# Check-Sheet.net
KiCad netlist of a schematic drawn in Altium Designer
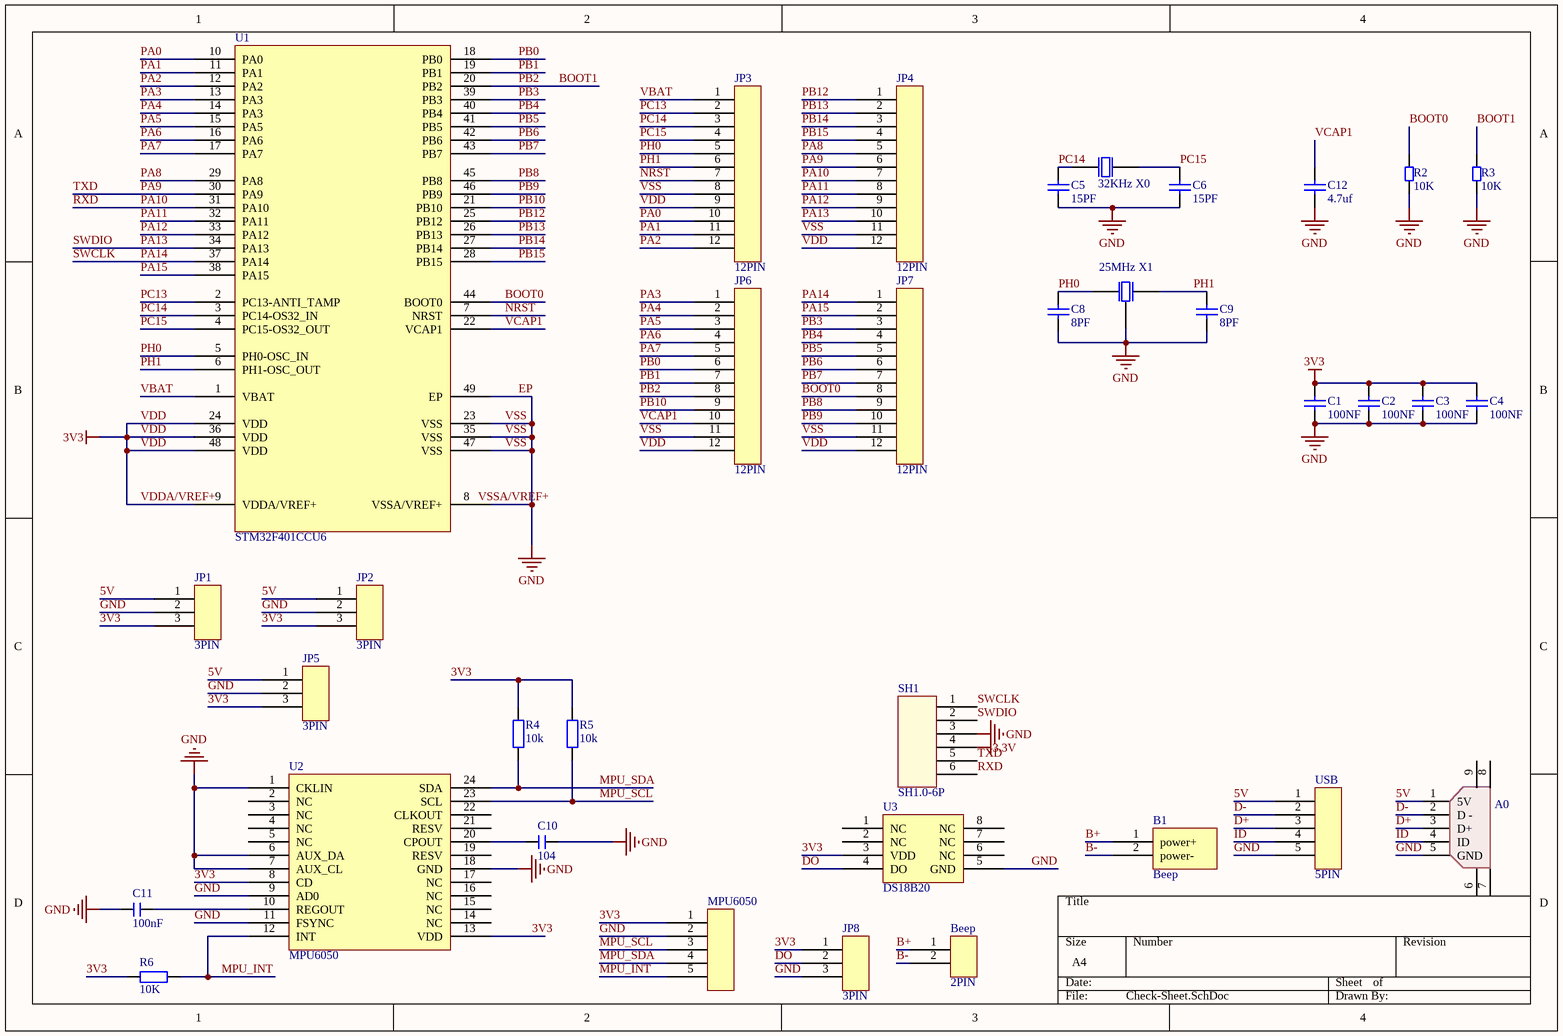
[diagram p0: Check-Sheet.SchDoc]

(export (version "E")
  (design (tool "Eeschema 10.0.6"))
  (components
    (comp (ref "25MHz X1")
      (value "XTAL 3225 8M")
      (footprint "OSC 3225-4P")
      (libsource (lib "tianxiaohua_Schlib") (part "XTAL 3225 8M"))
    )
    (comp (ref "32KHz X0")
      (value "XTAL 3215 32.768kKHz")
      (footprint "OSC 3215-2P")
      (libsource (lib "tianxiaohua_Schlib") (part "XTAL 3215 32.768kKHz"))
    )
    (comp (ref "A0")
      (value "Micro USB")
      (footprint "USB-micro_A")
      (libsource (lib "Schlib1") (part "Micro USB"))
    )
    (comp (ref "B1") (value "Beep") (footprint "5020beep") (libsource (lib "Schlib1") (part "Beep")))
    (comp (ref "Beep") (value "2PIN") (footprint "2PIN") (libsource (lib "Schlib1") (part "2PIN")))
    (comp (ref "C1")
      (value "100NF")
      (footprint "C 0603_M")
      (libsource (lib "tianxiaohua_Schlib") (part "0402 CAP"))
    )
    (comp (ref "C2")
      (value "100NF")
      (footprint "C 0603_M")
      (libsource (lib "tianxiaohua_Schlib") (part "0402 CAP"))
    )
    (comp (ref "C3")
      (value "100NF")
      (footprint "C 0603_M")
      (libsource (lib "tianxiaohua_Schlib") (part "0402 CAP"))
    )
    (comp (ref "C4")
      (value "100NF")
      (footprint "C 0603_M")
      (libsource (lib "tianxiaohua_Schlib") (part "0402 CAP"))
    )
    (comp (ref "C5")
      (value "15PF")
      (footprint "C 0603_M")
      (libsource (lib "tianxiaohua_Schlib") (part "0402 CAP"))
    )
    (comp (ref "C6")
      (value "15PF")
      (footprint "C 0603_M")
      (libsource (lib "tianxiaohua_Schlib") (part "0402 CAP"))
    )
    (comp (ref "C8")
      (value "8PF")
      (footprint "C 0603_M")
      (libsource (lib "tianxiaohua_Schlib") (part "0402 CAP"))
    )
    (comp (ref "C9")
      (value "8PF")
      (footprint "C 0603_M")
      (libsource (lib "tianxiaohua_Schlib") (part "0402 CAP"))
    )
    (comp (ref "C10")
      (value "104")
      (footprint "C 0805_L")
      (description "无极性贴片电容")
      (fields (field (name "版权归属") "源创客"))
      (libsource (lib "3.1   - 电阻-电容-电感") (part "C"))
    )
    (comp (ref "C11")
      (value "100nF")
      (footprint "C 0805_L")
      (description "无极性贴片电容")
      (fields (field (name "版权归属") "源创客"))
      (libsource (lib "3.1   - 电阻-电容-电感") (part "C"))
    )
    (comp (ref "C12")
      (value "4.7uf")
      (footprint "C 0603_M")
      (description "Polarized Capacitor (Radial)")
      (fields (field (name "Comment") "Cap Chip 0603") (field (name "PUBLISHER") "Altium Limited"))
      (libsource (lib "tianxiaohua_Schlib") (part "Cap Chip 0603"))
    )
    (comp (ref "JP1") (value "3PIN") (footprint "3pin") (libsource (lib "Schlib1") (part "3PIN")))
    (comp (ref "JP2") (value "3PIN") (footprint "3pin") (libsource (lib "Schlib1") (part "3PIN")))
    (comp (ref "JP3") (value "12PIN") (footprint "12PIN") (libsource (lib "Schlib1") (part "12PIN")))
    (comp (ref "JP4") (value "12PIN") (footprint "12PIN") (libsource (lib "Schlib1") (part "12PIN")))
    (comp (ref "JP5") (value "3PIN") (footprint "3pin") (libsource (lib "Schlib1") (part "3PIN")))
    (comp (ref "JP6") (value "12PIN") (footprint "12PIN") (libsource (lib "Schlib1") (part "12PIN")))
    (comp (ref "JP7") (value "12PIN") (footprint "12PIN") (libsource (lib "Schlib1") (part "12PIN")))
    (comp (ref "JP8") (value "3PIN") (footprint "3pin") (libsource (lib "Schlib1") (part "3PIN")))
    (comp (ref "MPU6050") (value "5PIN") (footprint "5PIN") (libsource (lib "Schlib1") (part "5PIN")))
    (comp (ref "R2")
      (value "10K")
      (footprint "R 0603_M")
      (libsource (lib "tianxiaohua_Schlib") (part "0402 RES"))
    )
    (comp (ref "R3")
      (value "10K")
      (footprint "R 0603_M")
      (libsource (lib "tianxiaohua_Schlib") (part "0402 RES"))
    )
    (comp (ref "R4")
      (value "10k")
      (footprint "0603R")
      (description "贴片电阻")
      (fields (field (name "版权归属") "源创客"))
      (libsource (lib "3.1   - 电阻-电容-电感") (part "R"))
    )
    (comp (ref "R5")
      (value "10k")
      (footprint "0603R")
      (description "贴片电阻")
      (fields (field (name "版权归属") "源创客"))
      (libsource (lib "3.1   - 电阻-电容-电感") (part "R"))
    )
    (comp (ref "R6")
      (value "10K")
      (footprint "0603R")
      (description "贴片电阻")
      (fields (field (name "版权归属") "源创客"))
      (libsource (lib "3.1   - 电阻-电容-电感") (part "R"))
    )
    (comp (ref "SH1")
      (value "SH1.0-6P")
      (footprint "6PIN")
      (description "间距为1mm的端子")
      (libsource (lib "tianxiaohua_Schlib") (part "SH1.0-6P"))
    )
    (comp (ref "U1")
      (value "STM32F401CCU6")
      (footprint "QFN48 7X7_M")
      (libsource (lib "Schlib1") (part "STM32F401CCU6"))
    )
    (comp (ref "U2") (value "MPU6050") (footprint "QFN24") (libsource (lib "Schlib1") (part "MPU6050")))
    (comp (ref "U3") (value "DS18B20") (footprint "SOP8") (libsource (lib "Schlib1") (part "DS18B20")))
    (comp (ref "USB") (value "5PIN") (footprint "5PIN") (libsource (lib "Schlib1") (part "5PIN")))
  )
  (nets
    (net (code "1") (name "/5V") (class "Default")
      (node (ref "A0") (pin "1") (pinfunction "5V_1") (pintype "passive"))
      (node (ref "JP1") (pin "1") (pintype "passive"))
      (node (ref "JP2") (pin "1") (pintype "passive"))
      (node (ref "JP5") (pin "1") (pintype "passive"))
      (node (ref "USB") (pin "1") (pintype "passive"))
    )
    (net (code "2") (name "/B+") (class "Default")
      (node (ref "B1") (pin "1") (pinfunction "power+_1") (pintype "passive"))
      (node (ref "Beep") (pin "1") (pintype "passive"))
    )
    (net (code "3") (name "/B-") (class "Default")
      (node (ref "B1") (pin "2") (pinfunction "power-_2") (pintype "passive"))
      (node (ref "Beep") (pin "2") (pintype "passive"))
    )
    (net (code "4") (name "/BOOT0") (class "Default")
      (node (ref "JP7") (pin "8") (pintype "passive"))
      (node (ref "R2") (pin "2") (pinfunction "2_2") (pintype "passive"))
      (node (ref "U1") (pin "44") (pinfunction "BOOT0_44") (pintype "passive"))
    )
    (net (code "5") (name "/BOOT1") (class "Default")
      (node (ref "JP6") (pin "8") (pintype "passive"))
      (node (ref "R3") (pin "2") (pinfunction "2_2") (pintype "passive"))
      (node (ref "U1") (pin "20") (pinfunction "PB2_20") (pintype "passive"))
    )
    (net (code "6") (name "/D+") (class "Default")
      (node (ref "A0") (pin "3") (pinfunction "D+_3") (pintype "passive"))
      (node (ref "USB") (pin "3") (pintype "passive"))
    )
    (net (code "7") (name "/D-") (class "Default")
      (node (ref "A0") (pin "2") (pinfunction "D_-_2") (pintype "passive"))
      (node (ref "USB") (pin "2") (pintype "passive"))
    )
    (net (code "8") (name "/DO") (class "Default")
      (node (ref "JP8") (pin "2") (pintype "passive"))
      (node (ref "U3") (pin "4") (pinfunction "DO_4") (pintype "passive"))
    )
    (net (code "9") (name "/ID") (class "Default")
      (node (ref "A0") (pin "4") (pinfunction "ID_4") (pintype "passive"))
      (node (ref "USB") (pin "4") (pintype "passive"))
    )
    (net (code "10") (name "/MPU_INT") (class "Default")
      (node (ref "MPU6050") (pin "5") (pintype "passive"))
      (node (ref "R6") (pin "2") (pinfunction "2_2") (pintype "passive"))
      (node (ref "U2") (pin "12") (pinfunction "INT_12") (pintype "passive"))
    )
    (net (code "11") (name "/MPU_SCL") (class "Default")
      (node (ref "MPU6050") (pin "3") (pintype "passive"))
      (node (ref "R5") (pin "1") (pinfunction "1_1") (pintype "passive"))
      (node (ref "U2") (pin "23") (pinfunction "SCL_23") (pintype "passive"))
    )
    (net (code "12") (name "/MPU_SDA") (class "Default")
      (node (ref "MPU6050") (pin "4") (pintype "passive"))
      (node (ref "R4") (pin "1") (pinfunction "1_1") (pintype "passive"))
      (node (ref "U2") (pin "24") (pinfunction "SDA_24") (pintype "passive"))
    )
    (net (code "13") (name "/NRST") (class "Default")
      (node (ref "JP3") (pin "7") (pintype "passive"))
      (node (ref "U1") (pin "7") (pinfunction "NRST_7") (pintype "passive"))
    )
    (net (code "14") (name "/PA0") (class "Default")
      (node (ref "JP3") (pin "10") (pintype "passive"))
      (node (ref "U1") (pin "10") (pinfunction "PA0_10") (pintype "passive"))
    )
    (net (code "15") (name "/PA1") (class "Default")
      (node (ref "JP3") (pin "11") (pintype "passive"))
      (node (ref "U1") (pin "11") (pinfunction "PA1_11") (pintype "passive"))
    )
    (net (code "16") (name "/PA2") (class "Default")
      (node (ref "JP3") (pin "12") (pintype "passive"))
      (node (ref "U1") (pin "12") (pinfunction "PA2_12") (pintype "passive"))
    )
    (net (code "17") (name "/PA3") (class "Default")
      (node (ref "JP6") (pin "1") (pintype "passive"))
      (node (ref "U1") (pin "13") (pinfunction "PA3_13") (pintype "passive"))
    )
    (net (code "18") (name "/PA4") (class "Default")
      (node (ref "JP6") (pin "2") (pintype "passive"))
      (node (ref "U1") (pin "14") (pinfunction "PA3_14") (pintype "passive"))
    )
    (net (code "19") (name "/PA5") (class "Default")
      (node (ref "JP6") (pin "3") (pintype "passive"))
      (node (ref "U1") (pin "15") (pinfunction "PA5_15") (pintype "passive"))
    )
    (net (code "20") (name "/PA6") (class "Default")
      (node (ref "JP6") (pin "4") (pintype "passive"))
      (node (ref "U1") (pin "16") (pinfunction "PA6_16") (pintype "passive"))
    )
    (net (code "21") (name "/PA7") (class "Default")
      (node (ref "JP6") (pin "5") (pintype "passive"))
      (node (ref "U1") (pin "17") (pinfunction "PA7_17") (pintype "passive"))
    )
    (net (code "22") (name "/PA8") (class "Default")
      (node (ref "JP4") (pin "5") (pintype "passive"))
      (node (ref "U1") (pin "29") (pinfunction "PA8_29") (pintype "passive"))
    )
    (net (code "23") (name "/PA9") (class "Default")
      (node (ref "JP4") (pin "6") (pintype "passive"))
      (node (ref "SH1") (pin "5") (pintype "passive"))
      (node (ref "U1") (pin "30") (pinfunction "PA9_30") (pintype "passive"))
    )
    (net (code "24") (name "/PA10") (class "Default")
      (node (ref "JP4") (pin "7") (pintype "passive"))
      (node (ref "SH1") (pin "6") (pinfunction "6_6") (pintype "passive"))
      (node (ref "U1") (pin "31") (pinfunction "PA10_31") (pintype "passive"))
    )
    (net (code "25") (name "/PA11") (class "Default")
      (node (ref "JP4") (pin "8") (pintype "passive"))
      (node (ref "U1") (pin "32") (pinfunction "PA11_32") (pintype "passive"))
    )
    (net (code "26") (name "/PA12") (class "Default")
      (node (ref "JP4") (pin "9") (pintype "passive"))
      (node (ref "U1") (pin "33") (pinfunction "PA12_33") (pintype "passive"))
    )
    (net (code "27") (name "/PA13") (class "Default")
      (node (ref "JP4") (pin "10") (pintype "passive"))
      (node (ref "SH1") (pin "2") (pinfunction "2_2") (pintype "passive"))
      (node (ref "U1") (pin "34") (pinfunction "PA13_34") (pintype "passive"))
    )
    (net (code "28") (name "/PA14") (class "Default")
      (node (ref "JP7") (pin "1") (pintype "passive"))
      (node (ref "SH1") (pin "1") (pintype "passive"))
      (node (ref "U1") (pin "37") (pinfunction "PA14_37") (pintype "passive"))
    )
    (net (code "29") (name "/PA15") (class "Default")
      (node (ref "JP7") (pin "2") (pintype "passive"))
      (node (ref "U1") (pin "38") (pinfunction "PA15_38") (pintype "passive"))
    )
    (net (code "30") (name "/PB0") (class "Default")
      (node (ref "JP6") (pin "6") (pintype "passive"))
      (node (ref "U1") (pin "18") (pinfunction "PB0_18") (pintype "passive"))
    )
    (net (code "31") (name "/PB1") (class "Default")
      (node (ref "JP6") (pin "7") (pintype "passive"))
      (node (ref "U1") (pin "19") (pinfunction "PB1_19") (pintype "passive"))
    )
    (net (code "32") (name "/PB3") (class "Default")
      (node (ref "JP7") (pin "3") (pintype "passive"))
      (node (ref "U1") (pin "39") (pinfunction "PB3_39") (pintype "passive"))
    )
    (net (code "33") (name "/PB4") (class "Default")
      (node (ref "JP7") (pin "4") (pintype "passive"))
      (node (ref "U1") (pin "40") (pinfunction "PB4_40") (pintype "passive"))
    )
    (net (code "34") (name "/PB5") (class "Default")
      (node (ref "JP7") (pin "5") (pintype "passive"))
      (node (ref "U1") (pin "41") (pinfunction "PB5_41") (pintype "passive"))
    )
    (net (code "35") (name "/PB6") (class "Default")
      (node (ref "JP7") (pin "6") (pintype "passive"))
      (node (ref "U1") (pin "42") (pinfunction "PB6_42") (pintype "passive"))
    )
    (net (code "36") (name "/PB7") (class "Default")
      (node (ref "JP7") (pin "7") (pintype "passive"))
      (node (ref "U1") (pin "43") (pinfunction "PB7_43") (pintype "passive"))
    )
    (net (code "37") (name "/PB8") (class "Default")
      (node (ref "JP7") (pin "9") (pintype "passive"))
      (node (ref "U1") (pin "45") (pinfunction "PB8_45") (pintype "passive"))
    )
    (net (code "38") (name "/PB9") (class "Default")
      (node (ref "JP7") (pin "10") (pintype "passive"))
      (node (ref "U1") (pin "46") (pinfunction "PB9_46") (pintype "passive"))
    )
    (net (code "39") (name "/PB10") (class "Default")
      (node (ref "JP6") (pin "9") (pintype "passive"))
      (node (ref "U1") (pin "21") (pinfunction "PB10_21") (pintype "passive"))
    )
    (net (code "40") (name "/PB12") (class "Default")
      (node (ref "JP4") (pin "1") (pintype "passive"))
      (node (ref "U1") (pin "25") (pinfunction "PB12_25") (pintype "passive"))
    )
    (net (code "41") (name "/PB13") (class "Default")
      (node (ref "JP4") (pin "2") (pintype "passive"))
      (node (ref "U1") (pin "26") (pinfunction "PB13_26") (pintype "passive"))
    )
    (net (code "42") (name "/PB14") (class "Default")
      (node (ref "JP4") (pin "3") (pintype "passive"))
      (node (ref "U1") (pin "27") (pinfunction "PB14_27") (pintype "passive"))
    )
    (net (code "43") (name "/PB15") (class "Default")
      (node (ref "JP4") (pin "4") (pintype "passive"))
      (node (ref "U1") (pin "28") (pinfunction "PB15_28") (pintype "passive"))
    )
    (net (code "44") (name "/PC13") (class "Default")
      (node (ref "JP3") (pin "2") (pintype "passive"))
      (node (ref "U1") (pin "2") (pinfunction "PC13-ANTI_TAMP_2") (pintype "passive"))
    )
    (net (code "45") (name "/PC14") (class "Default")
      (node (ref "32KHz X0") (pin "1") (pinfunction "OSC1_1") (pintype "passive"))
      (node (ref "C5") (pin "2") (pinfunction "2_2") (pintype "passive"))
      (node (ref "JP3") (pin "3") (pintype "passive"))
      (node (ref "U1") (pin "3") (pinfunction "PC14-OS32_IN_3") (pintype "passive"))
    )
    (net (code "46") (name "/PC15") (class "Default")
      (node (ref "32KHz X0") (pin "2") (pinfunction "OSC2_2") (pintype "passive"))
      (node (ref "C6") (pin "2") (pinfunction "2_2") (pintype "passive"))
      (node (ref "JP3") (pin "4") (pintype "passive"))
      (node (ref "U1") (pin "4") (pinfunction "PC15-OS32_OUT_4") (pintype "passive"))
    )
    (net (code "47") (name "/PH0") (class "Default")
      (node (ref "25MHz X1") (pin "1") (pinfunction "OSC1_1") (pintype "passive"))
      (node (ref "C8") (pin "2") (pinfunction "2_2") (pintype "passive"))
      (node (ref "JP3") (pin "5") (pintype "passive"))
      (node (ref "U1") (pin "5") (pinfunction "PH0-OSC_IN_5") (pintype "passive"))
    )
    (net (code "48") (name "/PH1") (class "Default")
      (node (ref "25MHz X1") (pin "2") (pinfunction "OSC2_2") (pintype "passive"))
      (node (ref "C9") (pin "2") (pinfunction "2_2") (pintype "passive"))
      (node (ref "JP3") (pin "6") (pintype "passive"))
      (node (ref "U1") (pin "6") (pinfunction "PH1-OSC_OUT_6") (pintype "passive"))
    )
    (net (code "49") (name "/VBAT") (class "Default")
      (node (ref "JP3") (pin "1") (pintype "passive"))
      (node (ref "U1") (pin "1") (pinfunction "VBAT_1") (pintype "passive"))
    )
    (net (code "50") (name "/VCAP1") (class "Default")
      (node (ref "C12") (pin "2") (pinfunction "2_2") (pintype "passive"))
      (node (ref "JP6") (pin "10") (pintype "passive"))
      (node (ref "U1") (pin "22") (pinfunction "VCAP1_22") (pintype "passive"))
    )
    (net (code "52") (name "3.3V") (class "Default")
      (node (ref "SH1") (pin "4") (pinfunction "4_4") (pintype "passive"))
    )
    (net (code "53") (name "3V3") (class "Default")
      (node (ref "C1") (pin "2") (pinfunction "2_2") (pintype "passive"))
      (node (ref "C2") (pin "2") (pinfunction "2_2") (pintype "passive"))
      (node (ref "C3") (pin "2") (pinfunction "2_2") (pintype "passive"))
      (node (ref "C4") (pin "2") (pinfunction "2_2") (pintype "passive"))
      (node (ref "JP1") (pin "3") (pintype "passive"))
      (node (ref "JP2") (pin "3") (pintype "passive"))
      (node (ref "JP3") (pin "9") (pintype "passive"))
      (node (ref "JP4") (pin "12") (pintype "passive"))
      (node (ref "JP5") (pin "3") (pintype "passive"))
      (node (ref "JP6") (pin "12") (pintype "passive"))
      (node (ref "JP7") (pin "12") (pintype "passive"))
      (node (ref "JP8") (pin "1") (pintype "passive"))
      (node (ref "MPU6050") (pin "1") (pintype "passive"))
      (node (ref "R4") (pin "2") (pinfunction "2_2") (pintype "passive"))
      (node (ref "R5") (pin "2") (pinfunction "2_2") (pintype "passive"))
      (node (ref "R6") (pin "1") (pinfunction "1_1") (pintype "passive"))
      (node (ref "U1") (pin "24") (pinfunction "VDD_24") (pintype "passive"))
      (node (ref "U1") (pin "36") (pinfunction "VDD_36") (pintype "passive"))
      (node (ref "U1") (pin "48") (pinfunction "VDD_48") (pintype "passive"))
      (node (ref "U1") (pin "9") (pinfunction "VDDA/VREF+_9") (pintype "passive"))
      (node (ref "U2") (pin "13") (pinfunction "VDD_13") (pintype "passive"))
      (node (ref "U2") (pin "8") (pinfunction "CD_8") (pintype "passive"))
      (node (ref "U3") (pin "3") (pinfunction "VDD_3") (pintype "passive"))
    )
    (net (code "54") (name "GND") (class "Default")
      (node (ref "25MHz X1") (pin "3") (pinfunction "GND_3") (pintype "passive"))
      (node (ref "A0") (pin "5") (pinfunction "GND_5") (pintype "passive"))
      (node (ref "C1") (pin "1") (pinfunction "1_1") (pintype "passive"))
      (node (ref "C10") (pin "2") (pinfunction "2_2") (pintype "passive"))
      (node (ref "C11") (pin "1") (pinfunction "1_1") (pintype "passive"))
      (node (ref "C12") (pin "1") (pinfunction "1_1") (pintype "passive"))
      (node (ref "C2") (pin "1") (pinfunction "1_1") (pintype "passive"))
      (node (ref "C3") (pin "1") (pinfunction "1_1") (pintype "passive"))
      (node (ref "C4") (pin "1") (pinfunction "1_1") (pintype "passive"))
      (node (ref "C5") (pin "1") (pinfunction "1_1") (pintype "passive"))
      (node (ref "C6") (pin "1") (pinfunction "1_1") (pintype "passive"))
      (node (ref "C8") (pin "1") (pinfunction "1_1") (pintype "passive"))
      (node (ref "C9") (pin "1") (pinfunction "1_1") (pintype "passive"))
      (node (ref "JP1") (pin "2") (pintype "passive"))
      (node (ref "JP2") (pin "2") (pintype "passive"))
      (node (ref "JP3") (pin "8") (pintype "passive"))
      (node (ref "JP4") (pin "11") (pintype "passive"))
      (node (ref "JP5") (pin "2") (pintype "passive"))
      (node (ref "JP6") (pin "11") (pintype "passive"))
      (node (ref "JP7") (pin "11") (pintype "passive"))
      (node (ref "JP8") (pin "3") (pintype "passive"))
      (node (ref "MPU6050") (pin "2") (pintype "passive"))
      (node (ref "R2") (pin "1") (pinfunction "1_1") (pintype "passive"))
      (node (ref "R3") (pin "1") (pinfunction "1_1") (pintype "passive"))
      (node (ref "SH1") (pin "3") (pintype "passive"))
      (node (ref "U1") (pin "23") (pinfunction "VSS_23") (pintype "passive"))
      (node (ref "U1") (pin "35") (pinfunction "VSS_35") (pintype "passive"))
      (node (ref "U1") (pin "47") (pinfunction "VSS_47") (pintype "passive"))
      (node (ref "U1") (pin "49") (pinfunction "EP_49") (pintype "passive"))
      (node (ref "U1") (pin "8") (pinfunction "VSSA/VREF+_8") (pintype "passive"))
      (node (ref "U2") (pin "1") (pinfunction "CKLIN_1") (pintype "passive"))
      (node (ref "U2") (pin "11") (pinfunction "FSYNC_11") (pintype "passive"))
      (node (ref "U2") (pin "18") (pinfunction "GND_18") (pintype "passive"))
      (node (ref "U2") (pin "6") (pinfunction "AUX_DA_6") (pintype "passive"))
      (node (ref "U2") (pin "7") (pinfunction "AUX_CL_7") (pintype "passive"))
      (node (ref "U2") (pin "9") (pinfunction "AD0_9") (pintype "passive"))
      (node (ref "U3") (pin "5") (pinfunction "GND_5") (pintype "passive"))
      (node (ref "USB") (pin "5") (pintype "passive"))
    )
    (net (code "55") (name "Net-(U2-CPOUT)") (class "Default")
      (node (ref "C10") (pin "1") (pinfunction "1_1") (pintype "passive"))
      (node (ref "U2") (pin "20") (pinfunction "CPOUT_20") (pintype "passive"))
    )
    (net (code "56") (name "Net-(U2-REGOUT)") (class "Default")
      (node (ref "C11") (pin "2") (pinfunction "2_2") (pintype "passive"))
      (node (ref "U2") (pin "10") (pinfunction "REGOUT_10") (pintype "passive"))
    )
    (net (code "57") (name "unconnected-(A0-Pad6)") (class "Default")
      (node (ref "A0") (pin "6") (pinfunction "6_6") (pintype "passive"))
    )
    (net (code "58") (name "unconnected-(A0-Pad7)") (class "Default")
      (node (ref "A0") (pin "7") (pinfunction "7_7") (pintype "passive"))
    )
    (net (code "59") (name "unconnected-(A0-Pad8)") (class "Default")
      (node (ref "A0") (pin "8") (pinfunction "8_8") (pintype "passive"))
    )
    (net (code "60") (name "unconnected-(A0-Pad9)") (class "Default")
      (node (ref "A0") (pin "9") (pinfunction "9_9") (pintype "passive"))
    )
    (net (code "61") (name "unconnected-(U2-CLKOUT-Pad22)") (class "Default")
      (node (ref "U2") (pin "22") (pinfunction "CLKOUT_22") (pintype "passive"))
    )
    (net (code "62") (name "unconnected-(U2-NC-Pad2)") (class "Default")
      (node (ref "U2") (pin "2") (pinfunction "NC_2") (pintype "passive"))
    )
    (net (code "63") (name "unconnected-(U2-NC-Pad3)") (class "Default")
      (node (ref "U2") (pin "3") (pinfunction "NC_3") (pintype "passive"))
    )
    (net (code "64") (name "unconnected-(U2-NC-Pad4)") (class "Default")
      (node (ref "U2") (pin "4") (pinfunction "NC_4") (pintype "passive"))
    )
    (net (code "65") (name "unconnected-(U2-NC-Pad5)") (class "Default")
      (node (ref "U2") (pin "5") (pinfunction "NC_5") (pintype "passive"))
    )
    (net (code "66") (name "unconnected-(U2-NC-Pad14)") (class "Default")
      (node (ref "U2") (pin "14") (pinfunction "NC_14") (pintype "passive"))
    )
    (net (code "67") (name "unconnected-(U2-NC-Pad15)") (class "Default")
      (node (ref "U2") (pin "15") (pinfunction "NC_15") (pintype "passive"))
    )
    (net (code "68") (name "unconnected-(U2-NC-Pad16)") (class "Default")
      (node (ref "U2") (pin "16") (pinfunction "NC_16") (pintype "passive"))
    )
    (net (code "69") (name "unconnected-(U2-NC-Pad17)") (class "Default")
      (node (ref "U2") (pin "17") (pinfunction "NC_17") (pintype "passive"))
    )
    (net (code "70") (name "unconnected-(U2-RESV-Pad19)") (class "Default")
      (node (ref "U2") (pin "19") (pinfunction "RESV_19") (pintype "passive"))
    )
    (net (code "71") (name "unconnected-(U2-RESV-Pad21)") (class "Default")
      (node (ref "U2") (pin "21") (pinfunction "RESV_21") (pintype "passive"))
    )
    (net (code "72") (name "unconnected-(U3-NC-Pad1)") (class "Default")
      (node (ref "U3") (pin "1") (pinfunction "NC_1") (pintype "passive"))
    )
    (net (code "73") (name "unconnected-(U3-NC-Pad2)") (class "Default")
      (node (ref "U3") (pin "2") (pinfunction "NC_2") (pintype "passive"))
    )
    (net (code "74") (name "unconnected-(U3-NC-Pad6)") (class "Default")
      (node (ref "U3") (pin "6") (pinfunction "NC_6") (pintype "passive"))
    )
    (net (code "75") (name "unconnected-(U3-NC-Pad7)") (class "Default")
      (node (ref "U3") (pin "7") (pinfunction "NC_7") (pintype "passive"))
    )
    (net (code "76") (name "unconnected-(U3-NC-Pad8)") (class "Default")
      (node (ref "U3") (pin "8") (pinfunction "NC_8") (pintype "passive"))
    )
  )
)
